# bicicletta-sensor.net
KiCad netlist of a schematic drawn in EAGLE
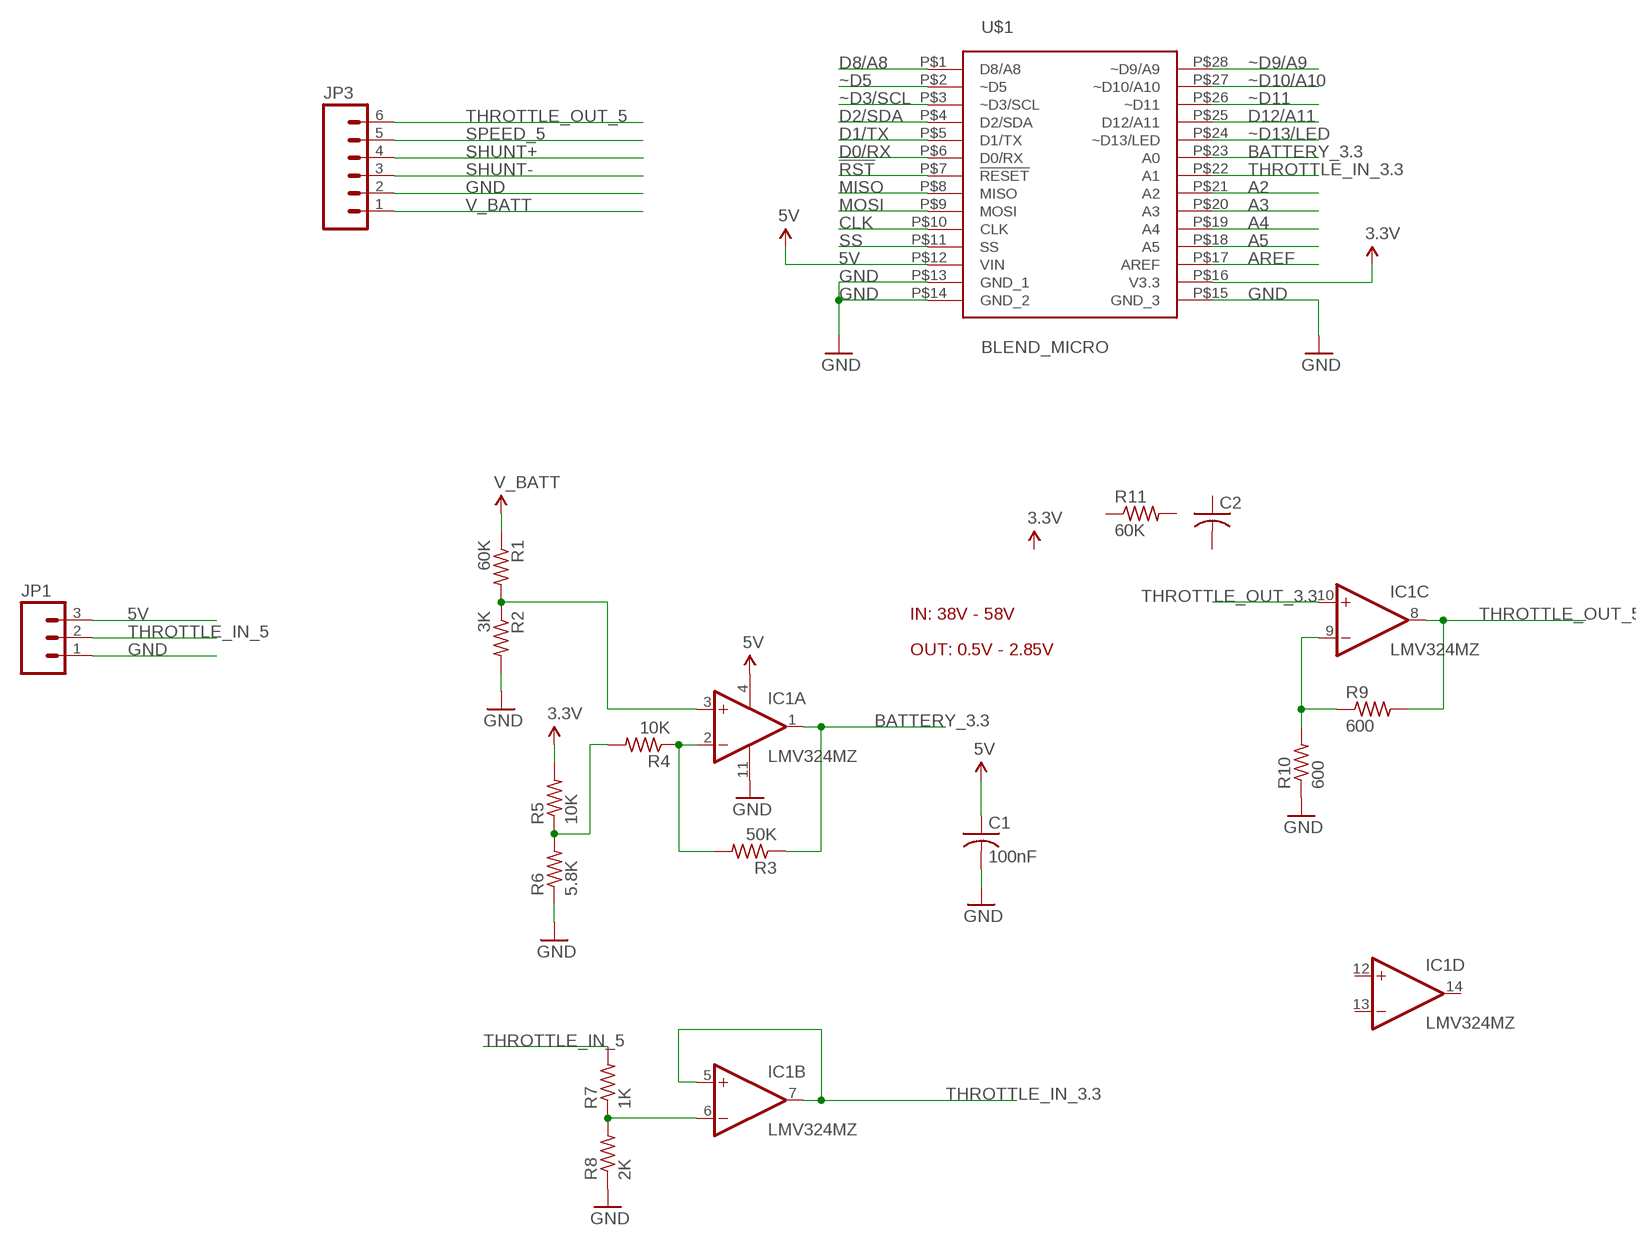
[diagram p0: schematic, sheet 1]

(export (version "E")
  (design (tool "Eeschema 10.0.6"))
  (components
    (comp (ref "C1")
      (value "100nF")
      (footprint "eagle-import:C0603")
      (libsource (lib "eagle-import") (part "C-USC0603"))
    )
    (comp (ref "C2")
      (value "C-USC0603")
      (footprint "eagle-import:C0603")
      (libsource (lib "eagle-import") (part "C-USC0603"))
    )
    (comp (ref "IC1")
      (value "LMV324MZ")
      (footprint "eagle-import:TSSOP14")
      (libsource (lib "eagle-import") (part "LMV324?MZ"))
    )
    (comp (ref "JP1")
      (value "M03PTH")
      (footprint "eagle-import:1X03")
      (libsource (lib "eagle-import") (part "M03PTH"))
    )
    (comp (ref "JP3")
      (value "M06SIP")
      (footprint "eagle-import:1X06")
      (libsource (lib "eagle-import") (part "M06SIP"))
    )
    (comp (ref "R1")
      (value "60K")
      (footprint "eagle-import:R0603")
      (libsource (lib "eagle-import") (part "R-US_R0603"))
    )
    (comp (ref "R2")
      (value "3K")
      (footprint "eagle-import:R0603")
      (libsource (lib "eagle-import") (part "R-US_R0603"))
    )
    (comp (ref "R3")
      (value "50K")
      (footprint "eagle-import:R0603")
      (libsource (lib "eagle-import") (part "R-US_R0603"))
    )
    (comp (ref "R4")
      (value "10K")
      (footprint "eagle-import:R0603")
      (libsource (lib "eagle-import") (part "R-US_R0603"))
    )
    (comp (ref "R5")
      (value "10K")
      (footprint "eagle-import:R0603")
      (libsource (lib "eagle-import") (part "R-US_R0603"))
    )
    (comp (ref "R6")
      (value "5.8K")
      (footprint "eagle-import:R0603")
      (libsource (lib "eagle-import") (part "R-US_R0603"))
    )
    (comp (ref "R7")
      (value "1K")
      (footprint "eagle-import:R0603")
      (libsource (lib "eagle-import") (part "R-US_R0603"))
    )
    (comp (ref "R8")
      (value "2K")
      (footprint "eagle-import:R0603")
      (libsource (lib "eagle-import") (part "R-US_R0603"))
    )
    (comp (ref "R9")
      (value "600")
      (footprint "eagle-import:R0603")
      (libsource (lib "eagle-import") (part "R-US_R0603"))
    )
    (comp (ref "R10")
      (value "600")
      (footprint "eagle-import:R0603")
      (libsource (lib "eagle-import") (part "R-US_R0603"))
    )
    (comp (ref "R11")
      (value "60K")
      (footprint "eagle-import:R0603")
      (libsource (lib "eagle-import") (part "R-US_R0603"))
    )
    (comp (ref "U$1")
      (value "BLEND_MICRO")
      (footprint "eagle-import:BLEND_MICRO")
      (libsource (lib "eagle-import") (part "BLEND_MICRO"))
    )
  )
  (nets
    (net (code "1") (name "/A2") (class "Default")
      (node (ref "U$1") (pin "P$21") (pinfunction "A2_P$21") (pintype "bidirectional"))
    )
    (net (code "2") (name "/A3") (class "Default")
      (node (ref "U$1") (pin "P$20") (pinfunction "A3_P$20") (pintype "bidirectional"))
    )
    (net (code "3") (name "/A4") (class "Default")
      (node (ref "U$1") (pin "P$19") (pinfunction "A4_P$19") (pintype "bidirectional"))
    )
    (net (code "4") (name "/A5") (class "Default")
      (node (ref "U$1") (pin "P$18") (pinfunction "A5_P$18") (pintype "bidirectional"))
    )
    (net (code "5") (name "/AREF") (class "Default")
      (node (ref "U$1") (pin "P$17") (pinfunction "AREF_P$17") (pintype "bidirectional"))
    )
    (net (code "6") (name "/BATTERY_3.3") (class "Default")
      (node (ref "IC1") (pin "1") (pinfunction "OUT_1") (pintype "output"))
      (node (ref "R3") (pin "1") (pinfunction "1_1") (pintype "passive"))
      (node (ref "U$1") (pin "P$23") (pinfunction "A0_P$23") (pintype "bidirectional"))
    )
    (net (code "7") (name "/CLK") (class "Default")
      (node (ref "U$1") (pin "P$10") (pinfunction "CLK_P$10") (pintype "bidirectional"))
    )
    (net (code "8") (name "/D0{slash}RX") (class "Default")
      (node (ref "U$1") (pin "P$6") (pinfunction "D0/RX_P$6") (pintype "bidirectional"))
    )
    (net (code "9") (name "/D1{slash}TX") (class "Default")
      (node (ref "U$1") (pin "P$5") (pinfunction "D1/TX_P$5") (pintype "bidirectional"))
    )
    (net (code "10") (name "/D2{slash}SDA") (class "Default")
      (node (ref "U$1") (pin "P$4") (pinfunction "D2/SDA_P$4") (pintype "bidirectional"))
    )
    (net (code "11") (name "/D8{slash}A8") (class "Default")
      (node (ref "U$1") (pin "P$1") (pinfunction "D8/A8_P$1") (pintype "bidirectional"))
    )
    (net (code "12") (name "/D12{slash}A11") (class "Default")
      (node (ref "U$1") (pin "P$25") (pinfunction "D12/A11_P$25") (pintype "bidirectional"))
    )
    (net (code "13") (name "/MISO") (class "Default")
      (node (ref "U$1") (pin "P$8") (pinfunction "MISO_P$8") (pintype "bidirectional"))
    )
    (net (code "14") (name "/MOSI") (class "Default")
      (node (ref "U$1") (pin "P$9") (pinfunction "MOSI_P$9") (pintype "bidirectional"))
    )
    (net (code "15") (name "/SHUNT+") (class "Default")
      (node (ref "JP3") (pin "4") (pinfunction "4_4") (pintype "passive"))
    )
    (net (code "16") (name "/SHUNT-") (class "Default")
      (node (ref "JP3") (pin "3") (pinfunction "3_3") (pintype "passive"))
    )
    (net (code "17") (name "/SPEED_5") (class "Default")
      (node (ref "JP3") (pin "5") (pinfunction "5_5") (pintype "passive"))
    )
    (net (code "18") (name "/SS") (class "Default")
      (node (ref "U$1") (pin "P$11") (pinfunction "SS_P$11") (pintype "bidirectional"))
    )
    (net (code "19") (name "/THROTTLE_IN_3.3") (class "Default")
      (node (ref "IC1") (pin "5") (pinfunction "+IN_5") (pintype "input"))
      (node (ref "IC1") (pin "7") (pinfunction "OUT_7") (pintype "output"))
      (node (ref "U$1") (pin "P$22") (pinfunction "A1_P$22") (pintype "bidirectional"))
    )
    (net (code "20") (name "/THROTTLE_IN_5") (class "Default")
      (node (ref "JP1") (pin "2") (pinfunction "2_2") (pintype "passive"))
      (node (ref "R7") (pin "2") (pinfunction "2_2") (pintype "passive"))
    )
    (net (code "21") (name "/THROTTLE_OUT_3.3") (class "Default")
      (node (ref "IC1") (pin "10") (pinfunction "+IN_10") (pintype "input"))
    )
    (net (code "22") (name "/THROTTLE_OUT_5") (class "Default")
      (node (ref "IC1") (pin "8") (pinfunction "OUT_8") (pintype "output"))
      (node (ref "JP3") (pin "6") (pinfunction "6_6") (pintype "passive"))
      (node (ref "R9") (pin "2") (pinfunction "2_2") (pintype "passive"))
    )
    (net (code "23") (name "/~{D3{slash}SCL}") (class "Default")
      (node (ref "U$1") (pin "P$3") (pinfunction "~{D3/SCL}_P$3") (pintype "bidirectional"))
    )
    (net (code "24") (name "/~{D5}") (class "Default")
      (node (ref "U$1") (pin "P$2") (pinfunction "~{D5}_P$2") (pintype "bidirectional"))
    )
    (net (code "25") (name "/~{D9{slash}A9}") (class "Default")
      (node (ref "U$1") (pin "P$28") (pinfunction "~{D9/A9}_P$28") (pintype "bidirectional"))
    )
    (net (code "26") (name "/~{D10{slash}A10}") (class "Default")
      (node (ref "U$1") (pin "P$27") (pinfunction "~{D10/A10}_P$27") (pintype "bidirectional"))
    )
    (net (code "27") (name "/~{D11}") (class "Default")
      (node (ref "U$1") (pin "P$26") (pinfunction "~{D11}_P$26") (pintype "bidirectional"))
    )
    (net (code "28") (name "/~{D13{slash}LED}") (class "Default")
      (node (ref "U$1") (pin "P$24") (pinfunction "~{D13/LED}_P$24") (pintype "bidirectional"))
    )
    (net (code "29") (name "/~{RST}") (class "Default")
      (node (ref "U$1") (pin "P$7") (pinfunction "~{RESET}_P$7") (pintype "bidirectional"))
    )
    (net (code "30") (name "3.3V") (class "Default")
      (node (ref "R5") (pin "2") (pinfunction "2_2") (pintype "passive"))
      (node (ref "U$1") (pin "P$16") (pinfunction "V3.3_P$16") (pintype "bidirectional"))
    )
    (net (code "31") (name "5V") (class "Default")
      (node (ref "C1") (pin "1") (pinfunction "1_1") (pintype "passive"))
      (node (ref "IC1") (pin "4") (pinfunction "V+_4") (pintype "power_in"))
      (node (ref "JP1") (pin "3") (pinfunction "3_3") (pintype "passive"))
      (node (ref "U$1") (pin "P$12") (pinfunction "VIN_P$12") (pintype "bidirectional"))
    )
    (net (code "32") (name "GND") (class "Default")
      (node (ref "C1") (pin "2") (pinfunction "2_2") (pintype "passive"))
      (node (ref "IC1") (pin "11") (pinfunction "V-_11") (pintype "power_in"))
      (node (ref "JP1") (pin "1") (pinfunction "1_1") (pintype "passive"))
      (node (ref "JP3") (pin "2") (pinfunction "2_2") (pintype "passive"))
      (node (ref "R10") (pin "1") (pinfunction "1_1") (pintype "passive"))
      (node (ref "R2") (pin "2") (pinfunction "2_2") (pintype "passive"))
      (node (ref "R6") (pin "1") (pinfunction "1_1") (pintype "passive"))
      (node (ref "R8") (pin "1") (pinfunction "1_1") (pintype "passive"))
      (node (ref "U$1") (pin "P$13") (pinfunction "GND_1_P$13") (pintype "bidirectional"))
      (node (ref "U$1") (pin "P$14") (pinfunction "GND_2_P$14") (pintype "bidirectional"))
      (node (ref "U$1") (pin "P$15") (pinfunction "GND_3_P$15") (pintype "bidirectional"))
    )
    (net (code "33") (name "Net-(IC1A-+IN)") (class "Default")
      (node (ref "IC1") (pin "3") (pinfunction "+IN_3") (pintype "input"))
      (node (ref "R1") (pin "2") (pinfunction "2_2") (pintype "passive"))
      (node (ref "R2") (pin "1") (pinfunction "1_1") (pintype "passive"))
    )
    (net (code "34") (name "Net-(IC1A--IN)") (class "Default")
      (node (ref "IC1") (pin "2") (pinfunction "-IN_2") (pintype "input"))
      (node (ref "R3") (pin "2") (pinfunction "2_2") (pintype "passive"))
      (node (ref "R4") (pin "1") (pinfunction "1_1") (pintype "passive"))
    )
    (net (code "35") (name "Net-(IC1B--IN)") (class "Default")
      (node (ref "IC1") (pin "6") (pinfunction "-IN_6") (pintype "input"))
      (node (ref "R7") (pin "1") (pinfunction "1_1") (pintype "passive"))
      (node (ref "R8") (pin "2") (pinfunction "2_2") (pintype "passive"))
    )
    (net (code "36") (name "Net-(IC1C--IN)") (class "Default")
      (node (ref "IC1") (pin "9") (pinfunction "-IN_9") (pintype "input"))
      (node (ref "R10") (pin "2") (pinfunction "2_2") (pintype "passive"))
      (node (ref "R9") (pin "1") (pinfunction "1_1") (pintype "passive"))
    )
    (net (code "37") (name "Net-(R4-Pad2)") (class "Default")
      (node (ref "R4") (pin "2") (pinfunction "2_2") (pintype "passive"))
      (node (ref "R5") (pin "1") (pinfunction "1_1") (pintype "passive"))
      (node (ref "R6") (pin "2") (pinfunction "2_2") (pintype "passive"))
    )
    (net (code "38") (name "V_BATT") (class "Default")
      (node (ref "JP3") (pin "1") (pinfunction "1_1") (pintype "passive"))
      (node (ref "R1") (pin "1") (pinfunction "1_1") (pintype "passive"))
    )
    (net (code "39") (name "unconnected-(C2-Pad1)") (class "Default")
      (node (ref "C2") (pin "1") (pinfunction "1_1") (pintype "passive"))
    )
    (net (code "40") (name "unconnected-(C2-Pad2)") (class "Default")
      (node (ref "C2") (pin "2") (pinfunction "2_2") (pintype "passive"))
    )
    (net (code "41") (name "unconnected-(IC1D-+IN-Pad12)") (class "Default")
      (node (ref "IC1") (pin "12") (pinfunction "+IN_12") (pintype "input"))
    )
    (net (code "42") (name "unconnected-(IC1D--IN-Pad13)") (class "Default")
      (node (ref "IC1") (pin "13") (pinfunction "-IN_13") (pintype "input"))
    )
    (net (code "43") (name "unconnected-(IC1D-OUT-Pad14)") (class "Default")
      (node (ref "IC1") (pin "14") (pinfunction "OUT_14") (pintype "output"))
    )
    (net (code "44") (name "unconnected-(R11-Pad1)") (class "Default")
      (node (ref "R11") (pin "1") (pinfunction "1_1") (pintype "passive"))
    )
    (net (code "45") (name "unconnected-(R11-Pad2)") (class "Default")
      (node (ref "R11") (pin "2") (pinfunction "2_2") (pintype "passive"))
    )
  )
)
